# FlightControl.net
KiCad netlist of a schematic drawn in EAGLE
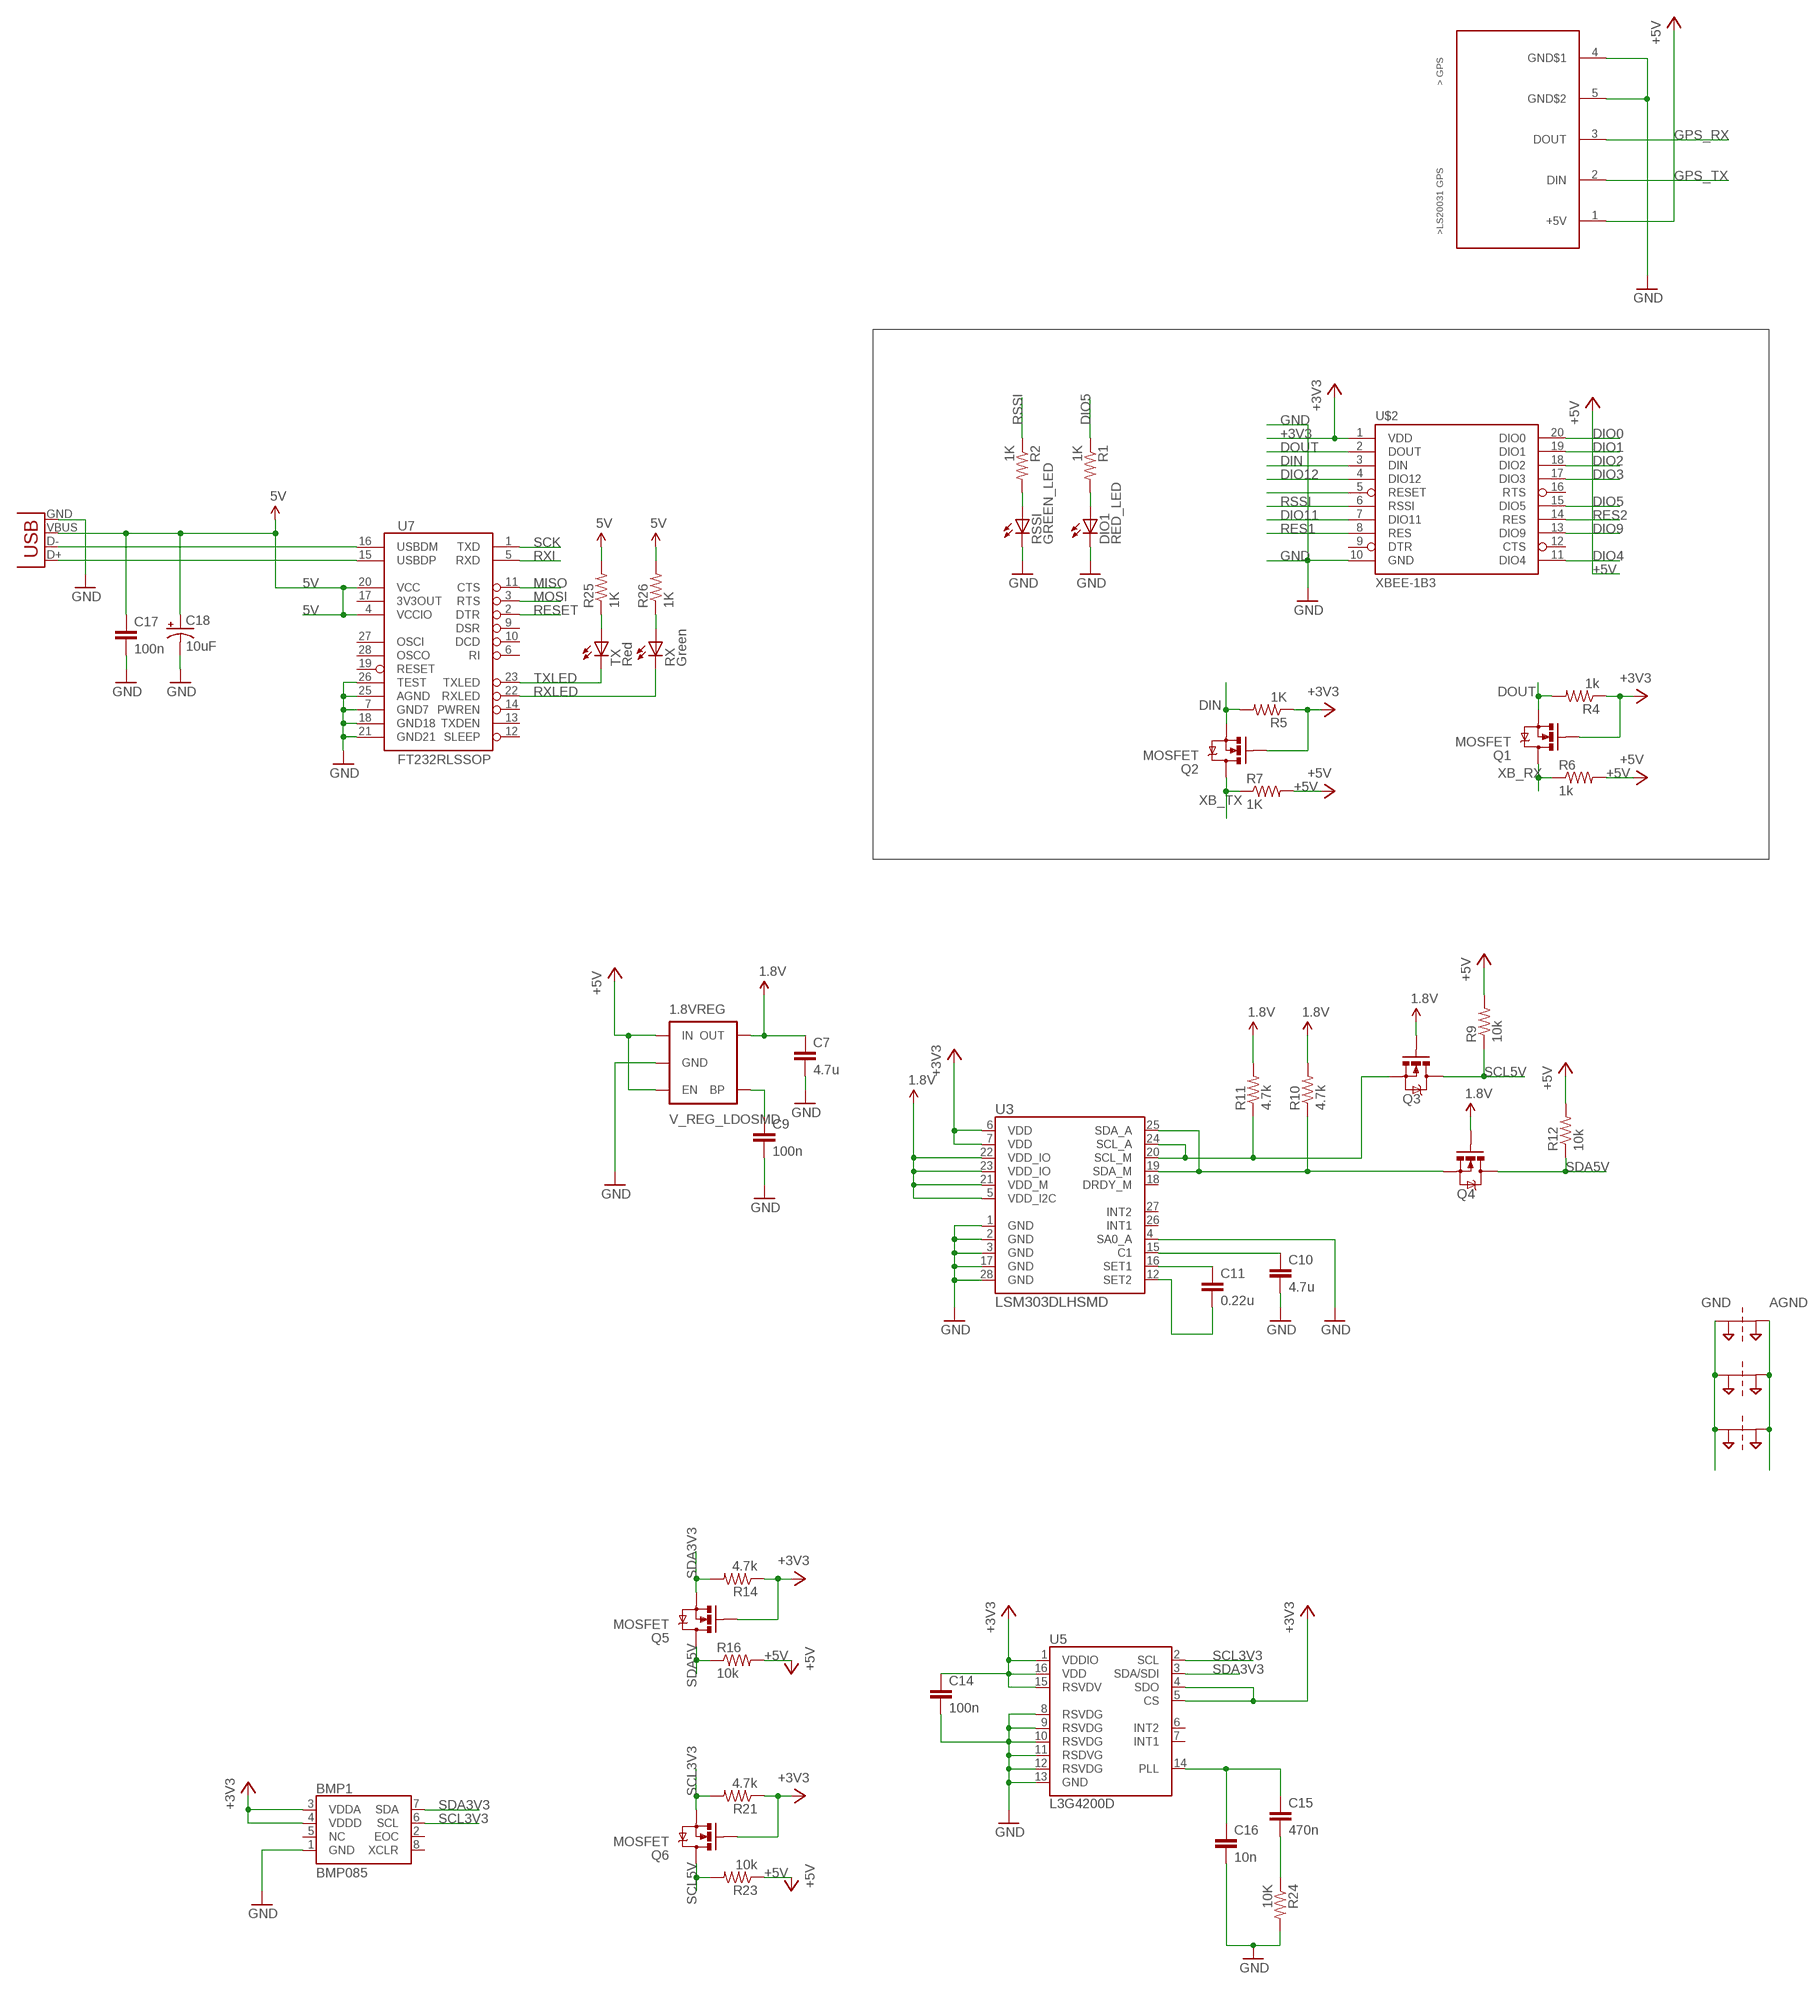
[diagram p0: schematic, sheet 1, part 1 of 2]
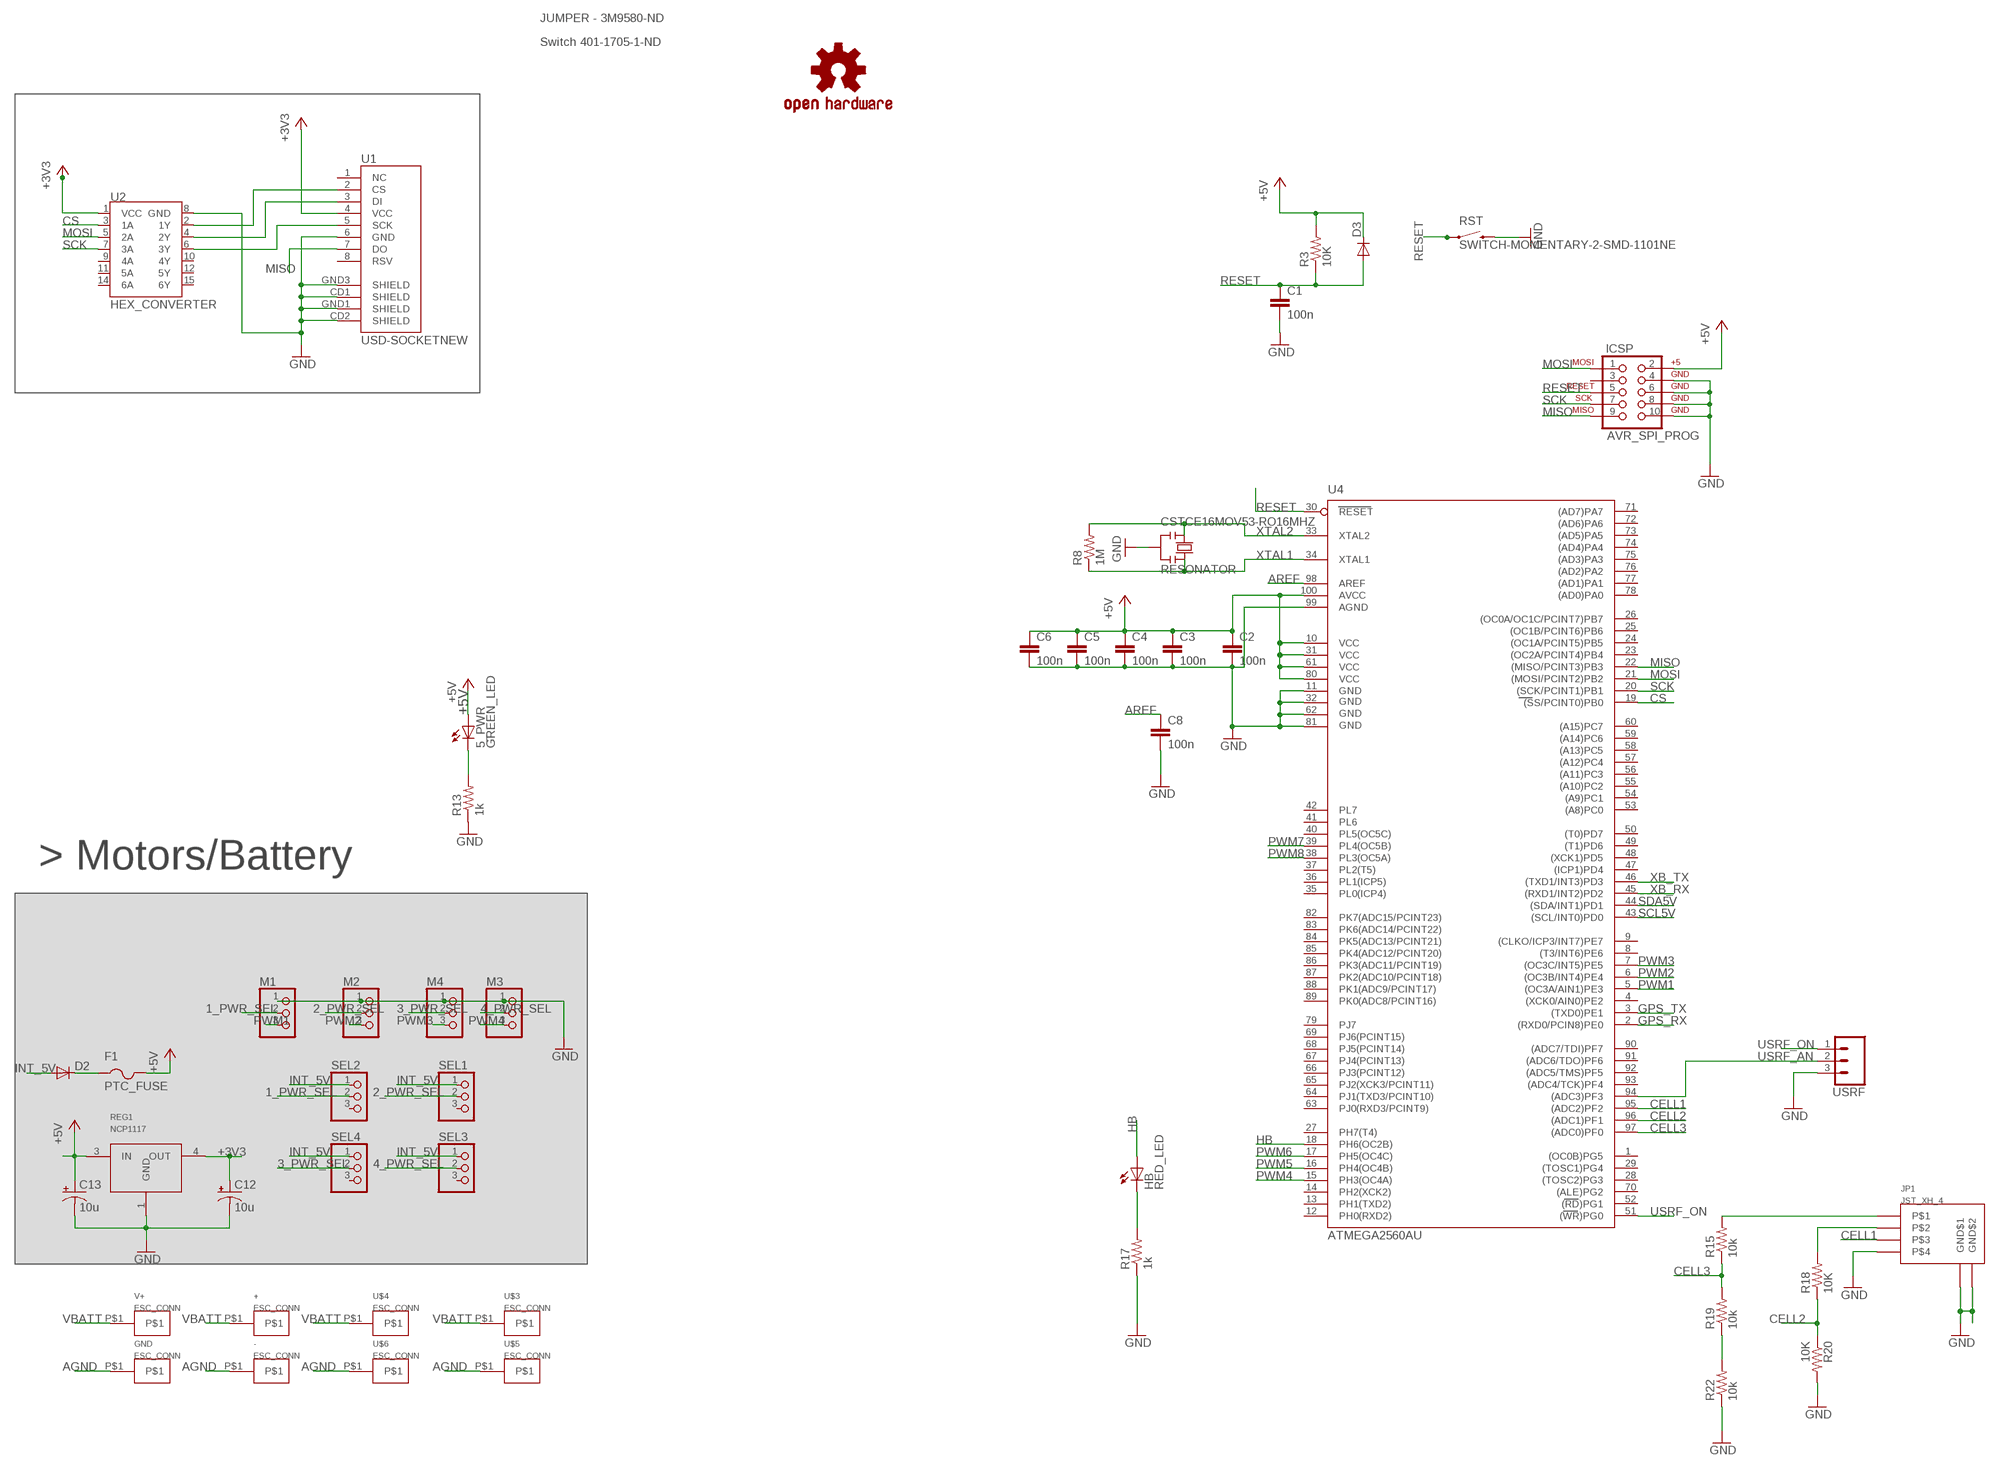
[diagram p1: schematic, sheet 1, part 2 of 2]

(export (version "E")
  (design (tool "Eeschema 10.0.6"))
  (components
    (comp (ref "+")
      (value "ESC_CONN")
      (footprint "eagle-import:ESC_CONN")
      (libsource (lib "eagle-import") (part "ESC_CONN"))
    )
    (comp (ref "-")
      (value "ESC_CONN")
      (footprint "eagle-import:ESC_CONN")
      (libsource (lib "eagle-import") (part "ESC_CONN"))
    )
    (comp (ref "1.8VREG")
      (value "V_REG_LDOSMD")
      (footprint "eagle-import:SOT23-5")
      (libsource (lib "eagle-import") (part "V_REG_LDOSMD"))
    )
    (comp (ref "5_PWR")
      (value "GREEN_LED")
      (footprint "eagle-import:LED-0603")
      (libsource (lib "eagle-import") (part "SparkFun-LED_LED0603"))
    )
    (comp (ref "BMP1")
      (value "BMP085")
      (footprint "eagle-import:BMP085")
      (libsource (lib "eagle-import") (part "BMP085"))
    )
    (comp (ref "C1")
      (value "100n")
      (footprint "eagle-import:0402-CAP")
      (libsource (lib "eagle-import") (part "SparkFun-Passives_CAP0402-CAP"))
    )
    (comp (ref "C2")
      (value "100n")
      (footprint "eagle-import:0402-CAP")
      (libsource (lib "eagle-import") (part "SparkFun-Passives_CAP0402-CAP"))
    )
    (comp (ref "C3")
      (value "100n")
      (footprint "eagle-import:0402-CAP")
      (libsource (lib "eagle-import") (part "SparkFun-Passives_CAP0402-CAP"))
    )
    (comp (ref "C4")
      (value "100n")
      (footprint "eagle-import:0402-CAP")
      (libsource (lib "eagle-import") (part "SparkFun-Passives_CAP0402-CAP"))
    )
    (comp (ref "C5")
      (value "100n")
      (footprint "eagle-import:0402-CAP")
      (libsource (lib "eagle-import") (part "SparkFun-Passives_CAP0402-CAP"))
    )
    (comp (ref "C6")
      (value "100n")
      (footprint "eagle-import:0402-CAP")
      (libsource (lib "eagle-import") (part "SparkFun-Passives_CAP0402-CAP"))
    )
    (comp (ref "C7")
      (value "4.7u")
      (footprint "eagle-import:0402-CAP")
      (libsource (lib "eagle-import") (part "SparkFun-Passives_CAP0402-CAP"))
    )
    (comp (ref "C8")
      (value "100n")
      (footprint "eagle-import:0402-CAP")
      (libsource (lib "eagle-import") (part "SparkFun-Passives_CAP0402-CAP"))
    )
    (comp (ref "C9")
      (value "100n")
      (footprint "eagle-import:0402-CAP")
      (libsource (lib "eagle-import") (part "SparkFun-Passives_CAP0402-CAP"))
    )
    (comp (ref "C10")
      (value "4.7u")
      (footprint "eagle-import:0402-CAP")
      (libsource (lib "eagle-import") (part "SparkFun-Passives_CAP0402-CAP"))
    )
    (comp (ref "C11")
      (value "0.22u")
      (footprint "eagle-import:0402-CAP")
      (libsource (lib "eagle-import") (part "SparkFun-Passives_CAP0402-CAP"))
    )
    (comp (ref "C12")
      (value "10u")
      (footprint "eagle-import:EIA3216")
      (libsource (lib "eagle-import") (part "SparkFun-Capacitors_CAP_POL1206"))
    )
    (comp (ref "C13")
      (value "10u")
      (footprint "eagle-import:EIA3216")
      (libsource (lib "eagle-import") (part "SparkFun-Capacitors_CAP_POL1206"))
    )
    (comp (ref "C14")
      (value "100n")
      (footprint "eagle-import:0402-CAP")
      (libsource (lib "eagle-import") (part "SparkFun-Capacitors_CAP0402-CAP"))
    )
    (comp (ref "C15")
      (value "470n")
      (footprint "eagle-import:0402-CAP")
      (libsource (lib "eagle-import") (part "SparkFun-Passives_CAP0402-CAP"))
    )
    (comp (ref "C16")
      (value "10n")
      (footprint "eagle-import:0402-CAP")
      (libsource (lib "eagle-import") (part "SparkFun-Passives_CAP0402-CAP"))
    )
    (comp (ref "C17")
      (value "100n")
      (footprint "eagle-import:0402-CAP")
      (libsource (lib "eagle-import") (part "CAP0402-CAP"))
    )
    (comp (ref "C18")
      (value "10uF")
      (footprint "eagle-import:EIA3216")
      (libsource (lib "eagle-import") (part "CAP_POL1206"))
    )
    (comp (ref "CSTCE16MOV53-RO16MHZ")
      (value "RESONATOR")
      (footprint "eagle-import:RESONATOR")
      (libsource (lib "eagle-import") (part "RESONATORMU"))
    )
    (comp (ref "D2")
      (value "SCHOTTKY-1206D1206")
      (footprint "eagle-import:C1206")
      (libsource (lib "eagle-import") (part "SCHOTTKY-1206D1206"))
    )
    (comp (ref "D3")
      (value "SCHOTTKY-1206D1206")
      (footprint "eagle-import:C1206")
      (libsource (lib "eagle-import") (part "SCHOTTKY-1206D1206"))
    )
    (comp (ref "DIO1")
      (value "RED_LED")
      (footprint "eagle-import:LED-0603")
      (libsource (lib "eagle-import") (part "SparkFun-LED_LED0603"))
    )
    (comp (ref "F1")
      (value "PTC_FUSE")
      (footprint "eagle-import:1812")
      (libsource (lib "eagle-import") (part "PTCFUSE-1812"))
    )
    (comp (ref "GND")
      (value "ESC_CONN")
      (footprint "eagle-import:ESC_CONN")
      (libsource (lib "eagle-import") (part "ESC_CONN"))
    )
    (comp (ref "HB")
      (value "RED_LED")
      (footprint "eagle-import:LED-0603")
      (libsource (lib "eagle-import") (part "SparkFun-LED_LED0603"))
    )
    (comp (ref "ICSP")
      (value "AVR_SPI_PROG")
      (footprint "eagle-import:AVR_ICSP")
      (libsource (lib "eagle-import") (part "AVR_SPI_PROG"))
    )
    (comp (ref "JP1")
      (value "JST_XH_4")
      (footprint "eagle-import:JST-XH4")
      (libsource (lib "eagle-import") (part "JST_XH_4"))
    )
    (comp (ref "LOGO1")
      (value "OSHW-LOGOL")
      (footprint "eagle-import:OSHW-LOGO-L")
      (libsource (lib "eagle-import") (part "OSHW-LOGOL"))
    )
    (comp (ref "M1")
      (value "PINHD-1X3")
      (footprint "eagle-import:1X03")
      (libsource (lib "eagle-import") (part "PINHD-1X3"))
    )
    (comp (ref "M2")
      (value "PINHD-1X3")
      (footprint "eagle-import:1X03")
      (libsource (lib "eagle-import") (part "PINHD-1X3"))
    )
    (comp (ref "M3")
      (value "PINHD-1X3")
      (footprint "eagle-import:1X03")
      (libsource (lib "eagle-import") (part "PINHD-1X3"))
    )
    (comp (ref "M4")
      (value "PINHD-1X3")
      (footprint "eagle-import:1X03")
      (libsource (lib "eagle-import") (part "PINHD-1X3"))
    )
    (comp (ref "PT1")
      (value "2PT_GND_TIE")
      (footprint "eagle-import:2PT_GND_TIE")
      (libsource (lib "eagle-import") (part "2PT_GND_TIE"))
    )
    (comp (ref "PT2")
      (value "2PT_GND_TIE")
      (footprint "eagle-import:2PT_GND_TIE")
      (libsource (lib "eagle-import") (part "2PT_GND_TIE"))
    )
    (comp (ref "PT3")
      (value "2PT_GND_TIE")
      (footprint "eagle-import:2PT_GND_TIE")
      (libsource (lib "eagle-import") (part "2PT_GND_TIE"))
    )
    (comp (ref "Q1")
      (value "MOSFET")
      (footprint "eagle-import:SOT23")
      (libsource (lib "eagle-import") (part "MOSFET-NCHANNELBSS138"))
    )
    (comp (ref "Q2")
      (value "MOSFET")
      (footprint "eagle-import:SOT23")
      (libsource (lib "eagle-import") (part "MOSFET-NCHANNELBSS138"))
    )
    (comp (ref "Q3")
      (value "MOSFET")
      (footprint "eagle-import:SOT23")
      (libsource (lib "eagle-import") (part "MOSFET-NCHANNELBSS138"))
    )
    (comp (ref "Q4")
      (value "MOSFET")
      (footprint "eagle-import:SOT23")
      (libsource (lib "eagle-import") (part "MOSFET-NCHANNELBSS138"))
    )
    (comp (ref "Q5")
      (value "MOSFET")
      (footprint "eagle-import:SOT23")
      (libsource (lib "eagle-import") (part "MOSFET-NCHANNELBSS138"))
    )
    (comp (ref "Q6")
      (value "MOSFET")
      (footprint "eagle-import:SOT23")
      (libsource (lib "eagle-import") (part "MOSFET-NCHANNELBSS138"))
    )
    (comp (ref "R1")
      (value "1K")
      (footprint "eagle-import:0603-RES")
      (libsource (lib "eagle-import") (part "RESISTOR0603-RES"))
    )
    (comp (ref "R2")
      (value "1K")
      (footprint "eagle-import:0603-RES")
      (libsource (lib "eagle-import") (part "RESISTOR0603-RES"))
    )
    (comp (ref "R3")
      (value "10K")
      (footprint "eagle-import:0603-RES")
      (libsource (lib "eagle-import") (part "RESISTOR0603-RES"))
    )
    (comp (ref "R4")
      (value "1k")
      (footprint "eagle-import:0603-RES")
      (libsource (lib "eagle-import") (part "RESISTOR0603-RES"))
    )
    (comp (ref "R5")
      (value "1K")
      (footprint "eagle-import:0603-RES")
      (libsource (lib "eagle-import") (part "RESISTOR0603-RES"))
    )
    (comp (ref "R6")
      (value "1k")
      (footprint "eagle-import:0603-RES")
      (libsource (lib "eagle-import") (part "RESISTOR0603-RES"))
    )
    (comp (ref "R7")
      (value "1K")
      (footprint "eagle-import:0603-RES")
      (libsource (lib "eagle-import") (part "RESISTOR0603-RES"))
    )
    (comp (ref "R8")
      (value "1M")
      (footprint "eagle-import:0603-RES")
      (libsource (lib "eagle-import") (part "RESISTOR0603-RES"))
    )
    (comp (ref "R9")
      (value "10k")
      (footprint "eagle-import:0603-RES")
      (libsource (lib "eagle-import") (part "RESISTOR0603-RES"))
    )
    (comp (ref "R10")
      (value "4.7k")
      (footprint "eagle-import:0402-RES")
      (libsource (lib "eagle-import") (part "RESISTOR0402-RES"))
    )
    (comp (ref "R11")
      (value "4.7k")
      (footprint "eagle-import:0603-RES")
      (libsource (lib "eagle-import") (part "RESISTOR0603-RES"))
    )
    (comp (ref "R12")
      (value "10k")
      (footprint "eagle-import:0603-RES")
      (libsource (lib "eagle-import") (part "RESISTOR0603-RES"))
    )
    (comp (ref "R13")
      (value "1k")
      (footprint "eagle-import:0603-RES")
      (libsource (lib "eagle-import") (part "RESISTOR0603-RES"))
    )
    (comp (ref "R14")
      (value "4.7k")
      (footprint "eagle-import:0603-RES")
      (libsource (lib "eagle-import") (part "RESISTOR0603-RES"))
    )
    (comp (ref "R15")
      (value "10k")
      (footprint "eagle-import:0603-RES")
      (libsource (lib "eagle-import") (part "RESISTOR0603-RES"))
    )
    (comp (ref "R16")
      (value "10k")
      (footprint "eagle-import:0603-RES")
      (libsource (lib "eagle-import") (part "RESISTOR0603-RES"))
    )
    (comp (ref "R17")
      (value "1k")
      (footprint "eagle-import:0603-RES")
      (libsource (lib "eagle-import") (part "RESISTOR0603-RES"))
    )
    (comp (ref "R18")
      (value "10K")
      (footprint "eagle-import:0603-RES")
      (libsource (lib "eagle-import") (part "RESISTOR0603-RES"))
    )
    (comp (ref "R19")
      (value "10k")
      (footprint "eagle-import:0603-RES")
      (libsource (lib "eagle-import") (part "RESISTOR0603-RES"))
    )
    (comp (ref "R20")
      (value "10K")
      (footprint "eagle-import:0603-RES")
      (libsource (lib "eagle-import") (part "RESISTOR0603-RES"))
    )
    (comp (ref "R21")
      (value "4.7k")
      (footprint "eagle-import:0603-RES")
      (libsource (lib "eagle-import") (part "RESISTOR0603-RES"))
    )
    (comp (ref "R22")
      (value "10k")
      (footprint "eagle-import:0603-RES")
      (libsource (lib "eagle-import") (part "RESISTOR0603-RES"))
    )
    (comp (ref "R23")
      (value "10k")
      (footprint "eagle-import:0603-RES")
      (libsource (lib "eagle-import") (part "RESISTOR0603-RES"))
    )
    (comp (ref "R24")
      (value "10K")
      (footprint "eagle-import:0603-RES")
      (libsource (lib "eagle-import") (part "RESISTOR0603-RES"))
    )
    (comp (ref "R25")
      (value "1K")
      (footprint "eagle-import:0603-RES")
      (libsource (lib "eagle-import") (part "RESISTOR0603-RES"))
    )
    (comp (ref "R26")
      (value "1K")
      (footprint "eagle-import:0603-RES")
      (libsource (lib "eagle-import") (part "RESISTOR0603-RES"))
    )
    (comp (ref "REG1")
      (value "NCP1117")
      (footprint "eagle-import:DPAK")
      (libsource (lib "eagle-import") (part "NCP1117"))
    )
    (comp (ref "RSSI")
      (value "GREEN_LED")
      (footprint "eagle-import:LED-0603")
      (libsource (lib "eagle-import") (part "SparkFun-LED_LED0603"))
    )
    (comp (ref "RST")
      (value "SWITCH-MOMENTARY-2-SMD-1101NE")
      (footprint "eagle-import:TACTILE-SWITCH-1101NE")
      (libsource (lib "eagle-import") (part "SWITCH-MOMENTARY-2-SMD-1101NE"))
    )
    (comp (ref "RX")
      (value "Green")
      (footprint "eagle-import:LED-0603")
      (libsource (lib "eagle-import") (part "LED0603"))
    )
    (comp (ref "SEL1")
      (value "PINHD-1X3")
      (footprint "eagle-import:1X03")
      (libsource (lib "eagle-import") (part "PINHD-1X3"))
    )
    (comp (ref "SEL2")
      (value "PINHD-1X3")
      (footprint "eagle-import:1X03")
      (libsource (lib "eagle-import") (part "PINHD-1X3"))
    )
    (comp (ref "SEL3")
      (value "PINHD-1X3")
      (footprint "eagle-import:1X03")
      (libsource (lib "eagle-import") (part "PINHD-1X3"))
    )
    (comp (ref "SEL4")
      (value "PINHD-1X3")
      (footprint "eagle-import:1X03")
      (libsource (lib "eagle-import") (part "PINHD-1X3"))
    )
    (comp (ref "TX")
      (value "Red")
      (footprint "eagle-import:LED-0603")
      (libsource (lib "eagle-import") (part "LED0603"))
    )
    (comp (ref "U$1")
      (value "LS20031")
      (footprint "eagle-import:LS20031")
      (libsource (lib "eagle-import") (part "LS20031"))
    )
    (comp (ref "U$2")
      (value "XBEE-1B3")
      (footprint "eagle-import:XBEE-SMD")
      (libsource (lib "eagle-import") (part "XBEE-1B3"))
    )
    (comp (ref "U$3")
      (value "ESC_CONN")
      (footprint "eagle-import:ESC_CONN")
      (libsource (lib "eagle-import") (part "ESC_CONN"))
    )
    (comp (ref "U$4")
      (value "ESC_CONN")
      (footprint "eagle-import:ESC_CONN")
      (libsource (lib "eagle-import") (part "ESC_CONN"))
    )
    (comp (ref "U$5")
      (value "ESC_CONN")
      (footprint "eagle-import:ESC_CONN")
      (libsource (lib "eagle-import") (part "ESC_CONN"))
    )
    (comp (ref "U$6")
      (value "ESC_CONN")
      (footprint "eagle-import:ESC_CONN")
      (libsource (lib "eagle-import") (part "ESC_CONN"))
    )
    (comp (ref "U1")
      (value "USD-SOCKETNEW")
      (footprint "eagle-import:MICRO-SD-SOCKET-PP")
      (libsource (lib "eagle-import") (part "USD-SOCKETNEW"))
    )
    (comp (ref "U2")
      (value "HEX_CONVERTER")
      (footprint "eagle-import:SO016")
      (libsource (lib "eagle-import") (part "HEX_CONVERTER"))
    )
    (comp (ref "U3")
      (value "LSM303DLHSMD")
      (footprint "eagle-import:LGA28-5X5")
      (libsource (lib "eagle-import") (part "LSM303DLHSMD"))
    )
    (comp (ref "U4")
      (value "ATMEGA2560AU")
      (footprint "eagle-import:TQFP100")
      (libsource (lib "eagle-import") (part "ATMEGA2560AU"))
    )
    (comp (ref "U5")
      (value "L3G4200D")
      (footprint "eagle-import:LGA16-4X4")
      (libsource (lib "eagle-import") (part "L3G4200D"))
    )
    (comp (ref "U7")
      (value "FT232RLSSOP")
      (footprint "eagle-import:SSOP28DB")
      (libsource (lib "eagle-import") (part "FT232RLSSOP"))
    )
    (comp (ref "USRF")
      (value "M03LOCK")
      (footprint "eagle-import:1X03_LOCK")
      (libsource (lib "eagle-import") (part "M03LOCK"))
    )
    (comp (ref "V+")
      (value "ESC_CONN")
      (footprint "eagle-import:ESC_CONN")
      (libsource (lib "eagle-import") (part "ESC_CONN"))
    )
    (comp (ref "X2")
      (value "USB-SMD-NS")
      (footprint "eagle-import:USB-MINIB-NOSTOP")
      (libsource (lib "eagle-import") (part "USB-SMD-NS"))
    )
  )
  (nets
    (net (code "1") (name "+3V3") (class "Default")
      (node (ref "BMP1") (pin "3") (pinfunction "VDDA_3") (pintype "power_in"))
      (node (ref "BMP1") (pin "4") (pinfunction "VDDD_4") (pintype "power_in"))
      (node (ref "C12") (pin "A") (pinfunction "+_A") (pintype "passive"))
      (node (ref "C14") (pin "1") (pinfunction "1_1") (pintype "passive"))
      (node (ref "Q1") (pin "1") (pinfunction "G_1") (pintype "passive"))
      (node (ref "Q2") (pin "1") (pinfunction "G_1") (pintype "passive"))
      (node (ref "Q5") (pin "1") (pinfunction "G_1") (pintype "passive"))
      (node (ref "Q6") (pin "1") (pinfunction "G_1") (pintype "passive"))
      (node (ref "R14") (pin "1") (pinfunction "1_1") (pintype "passive"))
      (node (ref "R21") (pin "1") (pinfunction "1_1") (pintype "passive"))
      (node (ref "R4") (pin "1") (pinfunction "1_1") (pintype "passive"))
      (node (ref "R5") (pin "1") (pinfunction "1_1") (pintype "passive"))
      (node (ref "REG1") (pin "4") (pinfunction "OUT_4") (pintype "bidirectional"))
      (node (ref "U$2") (pin "1") (pinfunction "VDD_1") (pintype "power_in"))
      (node (ref "U1") (pin "4") (pinfunction "VCC_4") (pintype "bidirectional"))
      (node (ref "U2") (pin "1") (pinfunction "VCC_1") (pintype "bidirectional"))
      (node (ref "U3") (pin "6") (pinfunction "VDD_6") (pintype "bidirectional"))
      (node (ref "U3") (pin "7") (pinfunction "VDD_7") (pintype "bidirectional"))
      (node (ref "U5") (pin "1") (pinfunction "VDDIO_1") (pintype "bidirectional"))
      (node (ref "U5") (pin "15") (pinfunction "RSVDV_15") (pintype "bidirectional"))
      (node (ref "U5") (pin "16") (pinfunction "VDD_16") (pintype "bidirectional"))
      (node (ref "U5") (pin "4") (pinfunction "SDO_4") (pintype "bidirectional"))
      (node (ref "U5") (pin "5") (pinfunction "CS_5") (pintype "bidirectional"))
    )
    (net (code "2") (name "+5V") (class "Default")
      (node (ref "1.8VREG") (pin "1") (pinfunction "IN_1") (pintype "input"))
      (node (ref "1.8VREG") (pin "3") (pinfunction "EN_3") (pintype "input"))
      (node (ref "5_PWR") (pin "A") (pinfunction "A_A") (pintype "passive"))
      (node (ref "C13") (pin "A") (pinfunction "+_A") (pintype "passive"))
      (node (ref "C2") (pin "1") (pinfunction "1_1") (pintype "passive"))
      (node (ref "C3") (pin "1") (pinfunction "1_1") (pintype "passive"))
      (node (ref "C4") (pin "1") (pinfunction "1_1") (pintype "passive"))
      (node (ref "C5") (pin "1") (pinfunction "1_1") (pintype "passive"))
      (node (ref "C6") (pin "1") (pinfunction "1_1") (pintype "passive"))
      (node (ref "D3") (pin "2") (pinfunction "C_2") (pintype "passive"))
      (node (ref "F1") (pin "2") (pinfunction "2_2") (pintype "passive"))
      (node (ref "ICSP") (pin "2") (pinfunction "2_2") (pintype "passive"))
      (node (ref "R12") (pin "2") (pinfunction "2_2") (pintype "passive"))
      (node (ref "R16") (pin "2") (pinfunction "2_2") (pintype "passive"))
      (node (ref "R23") (pin "1") (pinfunction "1_1") (pintype "passive"))
      (node (ref "R3") (pin "2") (pinfunction "2_2") (pintype "passive"))
      (node (ref "R6") (pin "2") (pinfunction "2_2") (pintype "passive"))
      (node (ref "R7") (pin "2") (pinfunction "2_2") (pintype "passive"))
      (node (ref "R9") (pin "2") (pinfunction "2_2") (pintype "passive"))
      (node (ref "REG1") (pin "3") (pinfunction "IN_3") (pintype "bidirectional"))
      (node (ref "U$1") (pin "1") (pinfunction "+5V_1") (pintype "bidirectional"))
      (node (ref "U4") (pin "10") (pinfunction "VCC_10") (pintype "power_in"))
      (node (ref "U4") (pin "100") (pinfunction "AVCC_100") (pintype "power_in"))
      (node (ref "U4") (pin "31") (pinfunction "VCC1_31") (pintype "power_in"))
      (node (ref "U4") (pin "61") (pinfunction "VCC2_61") (pintype "power_in"))
      (node (ref "U4") (pin "80") (pinfunction "VCC3_80") (pintype "power_in"))
    )
    (net (code "3") (name "/1_PWR_SEL") (class "Default")
      (node (ref "M1") (pin "2") (pinfunction "2_2") (pintype "passive"))
      (node (ref "SEL2") (pin "2") (pinfunction "2_2") (pintype "passive"))
    )
    (net (code "4") (name "/2_PWR_SEL") (class "Default")
      (node (ref "M2") (pin "2") (pinfunction "2_2") (pintype "passive"))
      (node (ref "SEL1") (pin "2") (pinfunction "2_2") (pintype "passive"))
    )
    (net (code "5") (name "/3_PWR_SEL") (class "Default")
      (node (ref "M4") (pin "2") (pinfunction "2_2") (pintype "passive"))
      (node (ref "SEL4") (pin "2") (pinfunction "2_2") (pintype "passive"))
    )
    (net (code "6") (name "/4_PWR_SEL") (class "Default")
      (node (ref "M3") (pin "2") (pinfunction "2_2") (pintype "passive"))
      (node (ref "SEL3") (pin "2") (pinfunction "2_2") (pintype "passive"))
    )
    (net (code "7") (name "/AGND") (class "Default")
      (node (ref "-") (pin "P$1") (pinfunction "P$1_P$1") (pintype "bidirectional"))
      (node (ref "GND") (pin "P$1") (pinfunction "P$1_P$1") (pintype "bidirectional"))
      (node (ref "PT1") (pin "P$2") (pinfunction "P$2_P$2") (pintype "bidirectional"))
      (node (ref "PT2") (pin "P$2") (pinfunction "P$2_P$2") (pintype "bidirectional"))
      (node (ref "PT3") (pin "P$2") (pinfunction "P$2_P$2") (pintype "bidirectional"))
      (node (ref "U$5") (pin "P$1") (pinfunction "P$1_P$1") (pintype "bidirectional"))
      (node (ref "U$6") (pin "P$1") (pinfunction "P$1_P$1") (pintype "bidirectional"))
    )
    (net (code "8") (name "/AREF") (class "Default")
      (node (ref "C8") (pin "1") (pinfunction "1_1") (pintype "passive"))
      (node (ref "U4") (pin "98") (pinfunction "AREF_98") (pintype "bidirectional"))
    )
    (net (code "9") (name "/CELL1") (class "Default")
      (node (ref "JP1") (pin "P$3") (pinfunction "P$3_P$3") (pintype "bidirectional"))
      (node (ref "U4") (pin "95") (pinfunction "(ADC2)PF2_95") (pintype "bidirectional"))
    )
    (net (code "10") (name "/CELL2") (class "Default")
      (node (ref "R18") (pin "1") (pinfunction "1_1") (pintype "passive"))
      (node (ref "R20") (pin "1") (pinfunction "1_1") (pintype "passive"))
      (node (ref "U4") (pin "96") (pinfunction "(ADC1)PF1_96") (pintype "bidirectional"))
    )
    (net (code "11") (name "/CELL3") (class "Default")
      (node (ref "R15") (pin "1") (pinfunction "1_1") (pintype "passive"))
      (node (ref "R19") (pin "2") (pinfunction "2_2") (pintype "passive"))
      (node (ref "U4") (pin "97") (pinfunction "(ADC0)PF0_97") (pintype "bidirectional"))
    )
    (net (code "12") (name "/CS") (class "Default")
      (node (ref "U2") (pin "3") (pinfunction "1A_3") (pintype "bidirectional"))
      (node (ref "U4") (pin "19") (pinfunction "(SS/PCINT0)PB0_19") (pintype "bidirectional"))
    )
    (net (code "13") (name "/DIN") (class "Default")
      (node (ref "Q2") (pin "2") (pinfunction "S_2") (pintype "passive"))
      (node (ref "R5") (pin "2") (pinfunction "2_2") (pintype "passive"))
      (node (ref "U$2") (pin "3") (pinfunction "DIN_3") (pintype "input"))
    )
    (net (code "14") (name "/DIO0") (class "Default")
      (node (ref "U$2") (pin "20") (pinfunction "DIO0_20") (pintype "bidirectional"))
    )
    (net (code "15") (name "/DIO1") (class "Default")
      (node (ref "U$2") (pin "19") (pinfunction "DIO1_19") (pintype "bidirectional"))
    )
    (net (code "16") (name "/DIO2") (class "Default")
      (node (ref "U$2") (pin "18") (pinfunction "DIO2_18") (pintype "bidirectional"))
    )
    (net (code "17") (name "/DIO3") (class "Default")
      (node (ref "U$2") (pin "17") (pinfunction "DIO3_17") (pintype "bidirectional"))
    )
    (net (code "18") (name "/DIO4") (class "Default")
      (node (ref "U$2") (pin "11") (pinfunction "DIO4_11") (pintype "bidirectional"))
    )
    (net (code "19") (name "/DIO5") (class "Default")
      (node (ref "R1") (pin "1") (pinfunction "1_1") (pintype "passive"))
      (node (ref "U$2") (pin "15") (pinfunction "DIO5_15") (pintype "bidirectional"))
    )
    (net (code "20") (name "/DIO9") (class "Default")
      (node (ref "U$2") (pin "13") (pinfunction "DIO9_13") (pintype "bidirectional"))
    )
    (net (code "21") (name "/DIO11") (class "Default")
      (node (ref "U$2") (pin "7") (pinfunction "DIO11_7") (pintype "bidirectional"))
    )
    (net (code "22") (name "/DIO12") (class "Default")
      (node (ref "U$2") (pin "4") (pinfunction "DIO12_4") (pintype "bidirectional"))
    )
    (net (code "23") (name "/DOUT") (class "Default")
      (node (ref "Q1") (pin "2") (pinfunction "S_2") (pintype "passive"))
      (node (ref "R4") (pin "2") (pinfunction "2_2") (pintype "passive"))
      (node (ref "U$2") (pin "2") (pinfunction "DOUT_2") (pintype "output"))
    )
    (net (code "24") (name "/GPS_RX") (class "Default")
      (node (ref "U$1") (pin "3") (pinfunction "DOUT_3") (pintype "output"))
      (node (ref "U4") (pin "2") (pinfunction "(RXD0/PCIN8)PE0_2") (pintype "bidirectional"))
    )
    (net (code "25") (name "/GPS_TX") (class "Default")
      (node (ref "U$1") (pin "2") (pinfunction "DIN_2") (pintype "bidirectional"))
      (node (ref "U4") (pin "3") (pinfunction "(TXD0)PE1_3") (pintype "bidirectional"))
    )
    (net (code "26") (name "/HB") (class "Default")
      (node (ref "HB") (pin "A") (pinfunction "A_A") (pintype "passive"))
      (node (ref "U4") (pin "18") (pinfunction "PH6(OC2B)_18") (pintype "bidirectional"))
    )
    (net (code "27") (name "/INT_5V") (class "Default")
      (node (ref "D2") (pin "1") (pinfunction "A_1") (pintype "passive"))
      (node (ref "SEL1") (pin "1") (pinfunction "1_1") (pintype "passive"))
      (node (ref "SEL2") (pin "1") (pinfunction "1_1") (pintype "passive"))
      (node (ref "SEL3") (pin "1") (pinfunction "1_1") (pintype "passive"))
      (node (ref "SEL4") (pin "1") (pinfunction "1_1") (pintype "passive"))
    )
    (net (code "28") (name "/MISO") (class "Default")
      (node (ref "ICSP") (pin "9") (pinfunction "9_9") (pintype "passive"))
      (node (ref "U1") (pin "7") (pinfunction "DO_7") (pintype "bidirectional"))
      (node (ref "U4") (pin "22") (pinfunction "(MISO/PCINT3)PB3_22") (pintype "bidirectional"))
      (node (ref "U7") (pin "11") (pinfunction "CTS_11") (pintype "input"))
    )
    (net (code "29") (name "/MOSI") (class "Default")
      (node (ref "ICSP") (pin "1") (pinfunction "1_1") (pintype "passive"))
      (node (ref "U2") (pin "5") (pinfunction "2A_5") (pintype "bidirectional"))
      (node (ref "U4") (pin "21") (pinfunction "(MOSI/PCINT2)PB2_21") (pintype "bidirectional"))
      (node (ref "U7") (pin "3") (pinfunction "RTS_3") (pintype "output"))
    )
    (net (code "30") (name "/PWM1") (class "Default")
      (node (ref "M1") (pin "3") (pinfunction "3_3") (pintype "passive"))
      (node (ref "U4") (pin "5") (pinfunction "(OC3A/AIN1)PE3_5") (pintype "bidirectional"))
    )
    (net (code "31") (name "/PWM2") (class "Default")
      (node (ref "M2") (pin "3") (pinfunction "3_3") (pintype "passive"))
      (node (ref "U4") (pin "6") (pinfunction "(OC3B/INT4)PE4_6") (pintype "bidirectional"))
    )
    (net (code "32") (name "/PWM3") (class "Default")
      (node (ref "M4") (pin "3") (pinfunction "3_3") (pintype "passive"))
      (node (ref "U4") (pin "7") (pinfunction "(OC3C/INT5)PE5_7") (pintype "bidirectional"))
    )
    (net (code "33") (name "/PWM4") (class "Default")
      (node (ref "M3") (pin "3") (pinfunction "3_3") (pintype "passive"))
      (node (ref "U4") (pin "15") (pinfunction "PH3(OC4A)_15") (pintype "bidirectional"))
    )
    (net (code "34") (name "/PWM5") (class "Default")
      (node (ref "U4") (pin "16") (pinfunction "PH4(OC4B)_16") (pintype "bidirectional"))
    )
    (net (code "35") (name "/PWM6") (class "Default")
      (node (ref "U4") (pin "17") (pinfunction "PH5(OC4C)_17") (pintype "bidirectional"))
    )
    (net (code "36") (name "/PWM7") (class "Default")
      (node (ref "U4") (pin "39") (pinfunction "PL4(OC5B)_39") (pintype "bidirectional"))
    )
    (net (code "37") (name "/PWM8") (class "Default")
      (node (ref "U4") (pin "38") (pinfunction "PL3(OC5A)_38") (pintype "bidirectional"))
    )
    (net (code "38") (name "/RES1") (class "Default")
      (node (ref "U$2") (pin "8") (pinfunction "RES_8") (pintype "bidirectional"))
    )
    (net (code "39") (name "/RES2") (class "Default")
      (node (ref "U$2") (pin "14") (pinfunction "RES_14") (pintype "bidirectional"))
    )
    (net (code "40") (name "/RESET") (class "Default")
      (node (ref "C1") (pin "1") (pinfunction "1_1") (pintype "passive"))
      (node (ref "D3") (pin "1") (pinfunction "A_1") (pintype "passive"))
      (node (ref "ICSP") (pin "5") (pinfunction "5_5") (pintype "passive"))
      (node (ref "R3") (pin "1") (pinfunction "1_1") (pintype "passive"))
      (node (ref "RST") (pin "P$1") (pinfunction "1_P$1") (pintype "passive"))
      (node (ref "U4") (pin "30") (pinfunction "RESET_30") (pintype "input"))
      (node (ref "U7") (pin "2") (pinfunction "DTR_2") (pintype "output"))
    )
    (net (code "41") (name "/RSSI") (class "Default")
      (node (ref "R2") (pin "1") (pinfunction "1_1") (pintype "passive"))
      (node (ref "U$2") (pin "6") (pinfunction "RSSI_6") (pintype "bidirectional"))
    )
    (net (code "42") (name "/RXI") (class "Default")
      (node (ref "U7") (pin "5") (pinfunction "RXD_5") (pintype "input"))
    )
    (net (code "43") (name "/RXLED") (class "Default")
      (node (ref "RX") (pin "C") (pinfunction "C_C") (pintype "passive"))
      (node (ref "U7") (pin "22") (pinfunction "RXLED_22") (pintype "input"))
    )
    (net (code "44") (name "/SCK") (class "Default")
      (node (ref "ICSP") (pin "7") (pinfunction "7_7") (pintype "passive"))
      (node (ref "U2") (pin "7") (pinfunction "3A_7") (pintype "bidirectional"))
      (node (ref "U4") (pin "20") (pinfunction "(SCK/PCINT1)PB1_20") (pintype "bidirectional"))
      (node (ref "U7") (pin "1") (pinfunction "TXD_1") (pintype "output"))
    )
    (net (code "45") (name "/SCL3V3") (class "Default")
      (node (ref "BMP1") (pin "6") (pinfunction "SCL_6") (pintype "input"))
      (node (ref "Q6") (pin "2") (pinfunction "S_2") (pintype "passive"))
      (node (ref "R21") (pin "2") (pinfunction "2_2") (pintype "passive"))
      (node (ref "U5") (pin "2") (pinfunction "SCL_2") (pintype "bidirectional"))
    )
    (net (code "46") (name "/SCL5V") (class "Default")
      (node (ref "Q3") (pin "3") (pinfunction "D_3") (pintype "passive"))
      (node (ref "Q6") (pin "3") (pinfunction "D_3") (pintype "passive"))
      (node (ref "R23") (pin "2") (pinfunction "2_2") (pintype "passive"))
      (node (ref "R9") (pin "1") (pinfunction "1_1") (pintype "passive"))
      (node (ref "U4") (pin "43") (pinfunction "(SCL/INT0)PD0_43") (pintype "bidirectional"))
    )
    (net (code "47") (name "/SDA3V3") (class "Default")
      (node (ref "BMP1") (pin "7") (pinfunction "SDA_7") (pintype "bidirectional"))
      (node (ref "Q5") (pin "2") (pinfunction "S_2") (pintype "passive"))
      (node (ref "R14") (pin "2") (pinfunction "2_2") (pintype "passive"))
      (node (ref "U5") (pin "3") (pinfunction "SDA/SDI_3") (pintype "bidirectional"))
    )
    (net (code "48") (name "/SDA5V") (class "Default")
      (node (ref "Q4") (pin "3") (pinfunction "D_3") (pintype "passive"))
      (node (ref "Q5") (pin "3") (pinfunction "D_3") (pintype "passive"))
      (node (ref "R12") (pin "1") (pinfunction "1_1") (pintype "passive"))
      (node (ref "R16") (pin "1") (pinfunction "1_1") (pintype "passive"))
      (node (ref "U4") (pin "44") (pinfunction "(SDA/INT1)PD1_44") (pintype "bidirectional"))
    )
    (net (code "49") (name "/TXLED") (class "Default")
      (node (ref "TX") (pin "C") (pinfunction "C_C") (pintype "passive"))
      (node (ref "U7") (pin "23") (pinfunction "TXLED_23") (pintype "input"))
    )
    (net (code "50") (name "/USRF_AN") (class "Default")
      (node (ref "U4") (pin "94") (pinfunction "(ADC3)PF3_94") (pintype "bidirectional"))
      (node (ref "USRF") (pin "2") (pinfunction "2_2") (pintype "passive"))
    )
    (net (code "51") (name "/USRF_ON") (class "Default")
      (node (ref "U4") (pin "51") (pinfunction "(WR)PG0_51") (pintype "bidirectional"))
      (node (ref "USRF") (pin "1") (pinfunction "1_1") (pintype "passive"))
    )
    (net (code "52") (name "/VBATT") (class "Default")
      (node (ref "+") (pin "P$1") (pinfunction "P$1_P$1") (pintype "bidirectional"))
      (node (ref "U$3") (pin "P$1") (pinfunction "P$1_P$1") (pintype "bidirectional"))
      (node (ref "U$4") (pin "P$1") (pinfunction "P$1_P$1") (pintype "bidirectional"))
      (node (ref "V+") (pin "P$1") (pinfunction "P$1_P$1") (pintype "bidirectional"))
    )
    (net (code "53") (name "/XB_RX") (class "Default")
      (node (ref "Q1") (pin "3") (pinfunction "D_3") (pintype "passive"))
      (node (ref "R6") (pin "1") (pinfunction "1_1") (pintype "passive"))
      (node (ref "U4") (pin "45") (pinfunction "(RXD1/INT2)PD2_45") (pintype "bidirectional"))
    )
    (net (code "54") (name "/XB_TX") (class "Default")
      (node (ref "Q2") (pin "3") (pinfunction "D_3") (pintype "passive"))
      (node (ref "R7") (pin "1") (pinfunction "1_1") (pintype "passive"))
      (node (ref "U4") (pin "46") (pinfunction "(TXD1/INT3)PD3_46") (pintype "bidirectional"))
    )
    (net (code "55") (name "/XTAL1") (class "Default")
      (node (ref "CSTCE16MOV53-RO16MHZ") (pin "3") (pinfunction "3_3") (pintype "passive"))
      (node (ref "R8") (pin "1") (pinfunction "1_1") (pintype "passive"))
      (node (ref "U4") (pin "34") (pinfunction "XTAL1_34") (pintype "input"))
    )
    (net (code "56") (name "/XTAL2") (class "Default")
      (node (ref "CSTCE16MOV53-RO16MHZ") (pin "1") (pinfunction "1_1") (pintype "passive"))
      (node (ref "R8") (pin "2") (pinfunction "2_2") (pintype "passive"))
      (node (ref "U4") (pin "33") (pinfunction "XTAL2_33") (pintype "output"))
    )
    (net (code "57") (name "1.8V") (class "Default")
      (node (ref "1.8VREG") (pin "5") (pinfunction "OUT_5") (pintype "passive"))
      (node (ref "C7") (pin "1") (pinfunction "1_1") (pintype "passive"))
      (node (ref "Q3") (pin "1") (pinfunction "G_1") (pintype "passive"))
      (node (ref "Q4") (pin "1") (pinfunction "G_1") (pintype "passive"))
      (node (ref "R10") (pin "2") (pinfunction "2_2") (pintype "passive"))
      (node (ref "R11") (pin "2") (pinfunction "2_2") (pintype "passive"))
      (node (ref "U3") (pin "21") (pinfunction "VDD_M_21") (pintype "bidirectional"))
      (node (ref "U3") (pin "22") (pinfunction "VDD_IO_22") (pintype "bidirectional"))
      (node (ref "U3") (pin "23") (pinfunction "VDD_IO_23") (pintype "bidirectional"))
      (node (ref "U3") (pin "5") (pinfunction "VDD_I2C_5") (pintype "bidirectional"))
    )
    (net (code "58") (name "5V") (class "Default")
      (node (ref "C17") (pin "1") (pinfunction "1_1") (pintype "passive"))
      (node (ref "C18") (pin "A") (pinfunction "+_A") (pintype "passive"))
      (node (ref "R25") (pin "2") (pinfunction "2_2") (pintype "passive"))
      (node (ref "R26") (pin "2") (pinfunction "2_2") (pintype "passive"))
      (node (ref "U7") (pin "20") (pinfunction "VCC_20") (pintype "power_in"))
      (node (ref "U7") (pin "4") (pinfunction "VCCIO_4") (pintype "power_in"))
      (node (ref "X2") (pin "VBUS") (pinfunction "VBUS_VBUS") (pintype "bidirectional"))
    )
    (net (code "59") (name "GND") (class "Default")
      (node (ref "1.8VREG") (pin "2") (pinfunction "GND_2") (pintype "input"))
      (node (ref "BMP1") (pin "1") (pinfunction "GND_1") (pintype "power_in"))
      (node (ref "C1") (pin "2") (pinfunction "2_2") (pintype "passive"))
      (node (ref "C10") (pin "2") (pinfunction "2_2") (pintype "passive"))
      (node (ref "C12") (pin "C") (pinfunction "-_C") (pintype "passive"))
      (node (ref "C13") (pin "C") (pinfunction "-_C") (pintype "passive"))
      (node (ref "C14") (pin "2") (pinfunction "2_2") (pintype "passive"))
      (node (ref "C16") (pin "2") (pinfunction "2_2") (pintype "passive"))
      (node (ref "C17") (pin "2") (pinfunction "2_2") (pintype "passive"))
      (node (ref "C18") (pin "C") (pinfunction "-_C") (pintype "passive"))
      (node (ref "C2") (pin "2") (pinfunction "2_2") (pintype "passive"))
      (node (ref "C3") (pin "2") (pinfunction "2_2") (pintype "passive"))
      (node (ref "C4") (pin "2") (pinfunction "2_2") (pintype "passive"))
      (node (ref "C5") (pin "2") (pinfunction "2_2") (pintype "passive"))
      (node (ref "C6") (pin "2") (pinfunction "2_2") (pintype "passive"))
      (node (ref "C7") (pin "2") (pinfunction "2_2") (pintype "passive"))
      (node (ref "C8") (pin "2") (pinfunction "2_2") (pintype "passive"))
      (node (ref "C9") (pin "2") (pinfunction "2_2") (pintype "passive"))
      (node (ref "CSTCE16MOV53-RO16MHZ") (pin "2") (pinfunction "2_2") (pintype "passive"))
      (node (ref "DIO1") (pin "C") (pinfunction "C_C") (pintype "passive"))
      (node (ref "ICSP") (pin "10") (pinfunction "10_10") (pintype "passive"))
      (node (ref "ICSP") (pin "4") (pinfunction "4_4") (pintype "passive"))
      (node (ref "ICSP") (pin "6") (pinfunction "6_6") (pintype "passive"))
      (node (ref "ICSP") (pin "8") (pinfunction "8_8") (pintype "passive"))
      (node (ref "JP1") (pin "GND$1") (pinfunction "GND$1_GND$1") (pintype "bidirectional"))
      (node (ref "JP1") (pin "GND$2") (pinfunction "GND$2_GND$2") (pintype "bidirectional"))
      (node (ref "JP1") (pin "P$4") (pinfunction "P$4_P$4") (pintype "bidirectional"))
      (node (ref "M1") (pin "1") (pinfunction "1_1") (pintype "passive"))
      (node (ref "M2") (pin "1") (pinfunction "1_1") (pintype "passive"))
      (node (ref "M3") (pin "1") (pinfunction "1_1") (pintype "passive"))
      (node (ref "M4") (pin "1") (pinfunction "1_1") (pintype "passive"))
      (node (ref "PT1") (pin "P$1") (pinfunction "P$1_P$1") (pintype "bidirectional"))
      (node (ref "PT2") (pin "P$1") (pinfunction "P$1_P$1") (pintype "bidirectional"))
      (node (ref "PT3") (pin "P$1") (pinfunction "P$1_P$1") (pintype "bidirectional"))
      (node (ref "R13") (pin "1") (pinfunction "1_1") (pintype "passive"))
      (node (ref "R17") (pin "1") (pinfunction "1_1") (pintype "passive"))
      (node (ref "R20") (pin "2") (pinfunction "2_2") (pintype "passive"))
      (node (ref "R22") (pin "1") (pinfunction "1_1") (pintype "passive"))
      (node (ref "R24") (pin "2") (pinfunction "2_2") (pintype "passive"))
      (node (ref "REG1") (pin "1") (pinfunction "GND_1") (pintype "bidirectional"))
      (node (ref "RSSI") (pin "C") (pinfunction "C_C") (pintype "passive"))
      (node (ref "RST") (pin "P$2") (pinfunction "2_P$2") (pintype "passive"))
      (node (ref "U$1") (pin "4") (pinfunction "GND$1_4") (pintype "bidirectional"))
      (node (ref "U$1") (pin "5") (pinfunction "GND$2_5") (pintype "bidirectional"))
      (node (ref "U$2") (pin "10") (pinfunction "GND_10") (pintype "power_in"))
      (node (ref "U1") (pin "6") (pinfunction "GND_6") (pintype "bidirectional"))
      (node (ref "U1") (pin "CD1") (pinfunction "SHIELD_CD1") (pintype "bidirectional"))
      (node (ref "U1") (pin "CD2") (pinfunction "SHIELD_CD2") (pintype "bidirectional"))
      (node (ref "U1") (pin "GND1") (pinfunction "SHIELD_GND1") (pintype "bidirectional"))
      (node (ref "U1") (pin "GND3") (pinfunction "SHIELD_GND3") (pintype "bidirectional"))
      (node (ref "U2") (pin "8") (pinfunction "GND_8") (pintype "bidirectional"))
      (node (ref "U3") (pin "1") (pinfunction "GND_1") (pintype "bidirectional"))
      (node (ref "U3") (pin "17") (pinfunction "GND_17") (pintype "bidirectional"))
      (node (ref "U3") (pin "2") (pinfunction "GND_2") (pintype "bidirectional"))
      (node (ref "U3") (pin "28") (pinfunction "GND_28") (pintype "bidirectional"))
      (node (ref "U3") (pin "3") (pinfunction "GND_3") (pintype "bidirectional"))
      (node (ref "U3") (pin "4") (pinfunction "SA0_A_4") (pintype "bidirectional"))
      (node (ref "U4") (pin "11") (pinfunction "GND_11") (pintype "power_in"))
      (node (ref "U4") (pin "32") (pinfunction "GND1_32") (pintype "power_in"))
      (node (ref "U4") (pin "62") (pinfunction "GND2_62") (pintype "power_in"))
      (node (ref "U4") (pin "81") (pinfunction "GND3_81") (pintype "power_in"))
      (node (ref "U4") (pin "99") (pinfunction "AGND_99") (pintype "power_in"))
      (node (ref "U5") (pin "10") (pinfunction "RSVDG_10") (pintype "bidirectional"))
      (node (ref "U5") (pin "11") (pinfunction "RSDVG_11") (pintype "bidirectional"))
      (node (ref "U5") (pin "12") (pinfunction "RSVDG_12") (pintype "bidirectional"))
      (node (ref "U5") (pin "13") (pinfunction "GND_13") (pintype "bidirectional"))
      (node (ref "U5") (pin "8") (pinfunction "RSVDG_8") (pintype "bidirectional"))
      (node (ref "U5") (pin "9") (pinfunction "RSVDG_9") (pintype "bidirectional"))
      (node (ref "U7") (pin "18") (pinfunction "GND18_18") (pintype "power_in"))
      (node (ref "U7") (pin "21") (pinfunction "GND21_21") (pintype "power_in"))
      (node (ref "U7") (pin "25") (pinfunction "AGND_25") (pintype "power_in"))
      (node (ref "U7") (pin "26") (pinfunction "TEST_26") (pintype "input"))
      (node (ref "U7") (pin "7") (pinfunction "GND7_7") (pintype "power_in"))
      (node (ref "USRF") (pin "3") (pinfunction "3_3") (pintype "passive"))
      (node (ref "X2") (pin "GND") (pinfunction "GND_GND") (pintype "bidirectional"))
    )
    (net (code "60") (name "Net-(1.8VREG-BP)") (class "Default")
      (node (ref "1.8VREG") (pin "4") (pinfunction "BP_4") (pintype "input"))
      (node (ref "C9") (pin "1") (pinfunction "1_1") (pintype "passive"))
    )
    (net (code "61") (name "Net-(5_PWR-PadC)") (class "Default")
      (node (ref "5_PWR") (pin "C") (pinfunction "C_C") (pintype "passive"))
      (node (ref "R13") (pin "2") (pinfunction "2_2") (pintype "passive"))
    )
    (net (code "62") (name "Net-(C15-Pad2)") (class "Default")
      (node (ref "C15") (pin "2") (pinfunction "2_2") (pintype "passive"))
      (node (ref "R24") (pin "1") (pinfunction "1_1") (pintype "passive"))
    )
    (net (code "63") (name "Net-(D2-C)") (class "Default")
      (node (ref "D2") (pin "2") (pinfunction "C_2") (pintype "passive"))
      (node (ref "F1") (pin "1") (pinfunction "1_1") (pintype "passive"))
    )
    (net (code "64") (name "Net-(DIO1-PadA)") (class "Default")
      (node (ref "DIO1") (pin "A") (pinfunction "A_A") (pintype "passive"))
      (node (ref "R1") (pin "2") (pinfunction "2_2") (pintype "passive"))
    )
    (net (code "65") (name "Net-(HB-PadC)") (class "Default")
      (node (ref "HB") (pin "C") (pinfunction "C_C") (pintype "passive"))
      (node (ref "R17") (pin "2") (pinfunction "2_2") (pintype "passive"))
    )
    (net (code "66") (name "Net-(JP1-PadP$1)") (class "Default")
      (node (ref "JP1") (pin "P$1") (pinfunction "P$1_P$1") (pintype "bidirectional"))
      (node (ref "R15") (pin "2") (pinfunction "2_2") (pintype "passive"))
    )
    (net (code "67") (name "Net-(JP1-PadP$2)") (class "Default")
      (node (ref "JP1") (pin "P$2") (pinfunction "P$2_P$2") (pintype "bidirectional"))
      (node (ref "R18") (pin "2") (pinfunction "2_2") (pintype "passive"))
    )
    (net (code "68") (name "Net-(Q3-S)") (class "Default")
      (node (ref "Q3") (pin "2") (pinfunction "S_2") (pintype "passive"))
      (node (ref "R11") (pin "1") (pinfunction "1_1") (pintype "passive"))
      (node (ref "U3") (pin "20") (pinfunction "SCL_M_20") (pintype "bidirectional"))
      (node (ref "U3") (pin "24") (pinfunction "SCL_A_24") (pintype "bidirectional"))
    )
    (net (code "69") (name "Net-(Q4-S)") (class "Default")
      (node (ref "Q4") (pin "2") (pinfunction "S_2") (pintype "passive"))
      (node (ref "R10") (pin "1") (pinfunction "1_1") (pintype "passive"))
      (node (ref "U3") (pin "19") (pinfunction "SDA_M_19") (pintype "bidirectional"))
      (node (ref "U3") (pin "25") (pinfunction "SDA_A_25") (pintype "bidirectional"))
    )
    (net (code "70") (name "Net-(R2-Pad2)") (class "Default")
      (node (ref "R2") (pin "2") (pinfunction "2_2") (pintype "passive"))
      (node (ref "RSSI") (pin "A") (pinfunction "A_A") (pintype "passive"))
    )
    (net (code "71") (name "Net-(R19-Pad1)") (class "Default")
      (node (ref "R19") (pin "1") (pinfunction "1_1") (pintype "passive"))
      (node (ref "R22") (pin "2") (pinfunction "2_2") (pintype "passive"))
    )
    (net (code "72") (name "Net-(R25-Pad1)") (class "Default")
      (node (ref "R25") (pin "1") (pinfunction "1_1") (pintype "passive"))
      (node (ref "TX") (pin "A") (pinfunction "A_A") (pintype "passive"))
    )
    (net (code "73") (name "Net-(R26-Pad1)") (class "Default")
      (node (ref "R26") (pin "1") (pinfunction "1_1") (pintype "passive"))
      (node (ref "RX") (pin "A") (pinfunction "A_A") (pintype "passive"))
    )
    (net (code "74") (name "Net-(U1-CS)") (class "Default")
      (node (ref "U1") (pin "2") (pinfunction "CS_2") (pintype "bidirectional"))
      (node (ref "U2") (pin "2") (pinfunction "1Y_2") (pintype "bidirectional"))
    )
    (net (code "75") (name "Net-(U1-DI)") (class "Default")
      (node (ref "U1") (pin "3") (pinfunction "DI_3") (pintype "bidirectional"))
      (node (ref "U2") (pin "4") (pinfunction "2Y_4") (pintype "bidirectional"))
    )
    (net (code "76") (name "Net-(U1-SCK)") (class "Default")
      (node (ref "U1") (pin "5") (pinfunction "SCK_5") (pintype "bidirectional"))
      (node (ref "U2") (pin "6") (pinfunction "3Y_6") (pintype "bidirectional"))
    )
    (net (code "77") (name "Net-(U3-C1)") (class "Default")
      (node (ref "C10") (pin "1") (pinfunction "1_1") (pintype "passive"))
      (node (ref "U3") (pin "15") (pinfunction "C1_15") (pintype "bidirectional"))
    )
    (net (code "78") (name "Net-(U3-SET1)") (class "Default")
      (node (ref "C11") (pin "1") (pinfunction "1_1") (pintype "passive"))
      (node (ref "U3") (pin "16") (pinfunction "SET1_16") (pintype "bidirectional"))
    )
    (net (code "79") (name "Net-(U3-SET2)") (class "Default")
      (node (ref "C11") (pin "2") (pinfunction "2_2") (pintype "passive"))
      (node (ref "U3") (pin "12") (pinfunction "SET2_12") (pintype "bidirectional"))
    )
    (net (code "80") (name "Net-(U5-PLL)") (class "Default")
      (node (ref "C15") (pin "1") (pinfunction "1_1") (pintype "passive"))
      (node (ref "C16") (pin "1") (pinfunction "1_1") (pintype "passive"))
      (node (ref "U5") (pin "14") (pinfunction "PLL_14") (pintype "bidirectional"))
    )
    (net (code "81") (name "Net-(U7-USBDM)") (class "Default")
      (node (ref "U7") (pin "16") (pinfunction "USBDM_16") (pintype "bidirectional"))
      (node (ref "X2") (pin "D-") (pinfunction "D-_D-") (pintype "bidirectional"))
    )
    (net (code "82") (name "Net-(U7-USBDP)") (class "Default")
      (node (ref "U7") (pin "15") (pinfunction "USBDP_15") (pintype "bidirectional"))
      (node (ref "X2") (pin "D+") (pinfunction "D+_D+") (pintype "bidirectional"))
    )
    (net (code "83") (name "unconnected-(BMP1-EOC-Pad2)") (class "Default")
      (node (ref "BMP1") (pin "2") (pinfunction "EOC_2") (pintype "output"))
    )
    (net (code "84") (name "unconnected-(BMP1-NC-Pad5)") (class "Default")
      (node (ref "BMP1") (pin "5") (pinfunction "NC_5") (pintype "bidirectional"))
    )
    (net (code "85") (name "unconnected-(BMP1-XCLR-Pad8)") (class "Default")
      (node (ref "BMP1") (pin "8") (pinfunction "XCLR_8") (pintype "input"))
    )
    (net (code "86") (name "unconnected-(ICSP-Pad3)") (class "Default")
      (node (ref "ICSP") (pin "3") (pinfunction "3_3") (pintype "passive"))
    )
    (net (code "87") (name "unconnected-(SEL1-Pad3)") (class "Default")
      (node (ref "SEL1") (pin "3") (pinfunction "3_3") (pintype "passive"))
    )
    (net (code "88") (name "unconnected-(SEL2-Pad3)") (class "Default")
      (node (ref "SEL2") (pin "3") (pinfunction "3_3") (pintype "passive"))
    )
    (net (code "89") (name "unconnected-(SEL3-Pad3)") (class "Default")
      (node (ref "SEL3") (pin "3") (pinfunction "3_3") (pintype "passive"))
    )
    (net (code "90") (name "unconnected-(SEL4-Pad3)") (class "Default")
      (node (ref "SEL4") (pin "3") (pinfunction "3_3") (pintype "passive"))
    )
    (net (code "91") (name "unconnected-(U$2-CTS-Pad12)") (class "Default")
      (node (ref "U$2") (pin "12") (pinfunction "CTS_12") (pintype "output"))
    )
    (net (code "92") (name "unconnected-(U$2-DTR-Pad9)") (class "Default")
      (node (ref "U$2") (pin "9") (pinfunction "DTR_9") (pintype "bidirectional"))
    )
    (net (code "93") (name "unconnected-(U$2-RESET-Pad5)") (class "Default")
      (node (ref "U$2") (pin "5") (pinfunction "RESET_5") (pintype "input"))
    )
    (net (code "94") (name "unconnected-(U$2-RTS-Pad16)") (class "Default")
      (node (ref "U$2") (pin "16") (pinfunction "RTS_16") (pintype "input"))
    )
    (net (code "95") (name "unconnected-(U1-NC-Pad1)") (class "Default")
      (node (ref "U1") (pin "1") (pinfunction "NC_1") (pintype "bidirectional"))
    )
    (net (code "96") (name "unconnected-(U1-RSV-Pad8)") (class "Default")
      (node (ref "U1") (pin "8") (pinfunction "RSV_8") (pintype "bidirectional"))
    )
    (net (code "97") (name "unconnected-(U2-4A-Pad9)") (class "Default")
      (node (ref "U2") (pin "9") (pinfunction "4A_9") (pintype "bidirectional"))
    )
    (net (code "98") (name "unconnected-(U2-4Y-Pad10)") (class "Default")
      (node (ref "U2") (pin "10") (pinfunction "4Y_10") (pintype "bidirectional"))
    )
    (net (code "99") (name "unconnected-(U2-5A-Pad11)") (class "Default")
      (node (ref "U2") (pin "11") (pinfunction "5A_11") (pintype "bidirectional"))
    )
    (net (code "100") (name "unconnected-(U2-5Y-Pad12)") (class "Default")
      (node (ref "U2") (pin "12") (pinfunction "5Y_12") (pintype "bidirectional"))
    )
    (net (code "101") (name "unconnected-(U2-6A-Pad14)") (class "Default")
      (node (ref "U2") (pin "14") (pinfunction "6A_14") (pintype "bidirectional"))
    )
    (net (code "102") (name "unconnected-(U2-6Y-Pad15)") (class "Default")
      (node (ref "U2") (pin "15") (pinfunction "6Y_15") (pintype "bidirectional"))
    )
    (net (code "103") (name "unconnected-(U3-DRDY_M-Pad18)") (class "Default")
      (node (ref "U3") (pin "18") (pinfunction "DRDY_M_18") (pintype "bidirectional"))
    )
    (net (code "104") (name "unconnected-(U3-INT1-Pad26)") (class "Default")
      (node (ref "U3") (pin "26") (pinfunction "INT1_26") (pintype "bidirectional"))
    )
    (net (code "105") (name "unconnected-(U3-INT2-Pad27)") (class "Default")
      (node (ref "U3") (pin "27") (pinfunction "INT2_27") (pintype "bidirectional"))
    )
    (net (code "106") (name "unconnected-(U4-(A8)PC0-Pad53)") (class "Default")
      (node (ref "U4") (pin "53") (pinfunction "(A8)PC0_53") (pintype "bidirectional"))
    )
    (net (code "107") (name "unconnected-(U4-(A9)PC1-Pad54)") (class "Default")
      (node (ref "U4") (pin "54") (pinfunction "(A9)PC1_54") (pintype "bidirectional"))
    )
    (net (code "108") (name "unconnected-(U4-(A10)PC2-Pad55)") (class "Default")
      (node (ref "U4") (pin "55") (pinfunction "(A10)PC2_55") (pintype "bidirectional"))
    )
    (net (code "109") (name "unconnected-(U4-(A11)PC3-Pad56)") (class "Default")
      (node (ref "U4") (pin "56") (pinfunction "(A11)PC3_56") (pintype "bidirectional"))
    )
    (net (code "110") (name "unconnected-(U4-(A12)PC4-Pad57)") (class "Default")
      (node (ref "U4") (pin "57") (pinfunction "(A12)PC4_57") (pintype "bidirectional"))
    )
    (net (code "111") (name "unconnected-(U4-(A13)PC5-Pad58)") (class "Default")
      (node (ref "U4") (pin "58") (pinfunction "(A13)PC5_58") (pintype "bidirectional"))
    )
    (net (code "112") (name "unconnected-(U4-(A14)PC6-Pad59)") (class "Default")
      (node (ref "U4") (pin "59") (pinfunction "(A14)PC6_59") (pintype "bidirectional"))
    )
    (net (code "113") (name "unconnected-(U4-(A15)PC7-Pad60)") (class "Default")
      (node (ref "U4") (pin "60") (pinfunction "(A15)PC7_60") (pintype "bidirectional"))
    )
    (net (code "114") (name "unconnected-(U4-(AD0)PA0-Pad78)") (class "Default")
      (node (ref "U4") (pin "78") (pinfunction "(AD0)PA0_78") (pintype "bidirectional"))
    )
    (net (code "115") (name "unconnected-(U4-(AD1)PA1-Pad77)") (class "Default")
      (node (ref "U4") (pin "77") (pinfunction "(AD1)PA1_77") (pintype "bidirectional"))
    )
    (net (code "116") (name "unconnected-(U4-(AD2)PA2-Pad76)") (class "Default")
      (node (ref "U4") (pin "76") (pinfunction "(AD2)PA2_76") (pintype "bidirectional"))
    )
    (net (code "117") (name "unconnected-(U4-(AD3)PA3-Pad75)") (class "Default")
      (node (ref "U4") (pin "75") (pinfunction "(AD3)PA3_75") (pintype "bidirectional"))
    )
    (net (code "118") (name "unconnected-(U4-(AD4)PA4-Pad74)") (class "Default")
      (node (ref "U4") (pin "74") (pinfunction "(AD4)PA4_74") (pintype "bidirectional"))
    )
    (net (code "119") (name "unconnected-(U4-(AD5)PA5-Pad73)") (class "Default")
      (node (ref "U4") (pin "73") (pinfunction "(AD5)PA5_73") (pintype "bidirectional"))
    )
    (net (code "120") (name "unconnected-(U4-(AD6)PA6-Pad72)") (class "Default")
      (node (ref "U4") (pin "72") (pinfunction "(AD6)PA6_72") (pintype "bidirectional"))
    )
    (net (code "121") (name "unconnected-(U4-(AD7)PA7-Pad71)") (class "Default")
      (node (ref "U4") (pin "71") (pinfunction "(AD7)PA7_71") (pintype "bidirectional"))
    )
    (net (code "122") (name "unconnected-(U4-(ADC4{slash}TCK)PF4-Pad93)") (class "Default")
      (node (ref "U4") (pin "93") (pinfunction "(ADC4/TCK)PF4_93") (pintype "bidirectional"))
    )
    (net (code "123") (name "unconnected-(U4-(ADC5{slash}TMS)PF5-Pad92)") (class "Default")
      (node (ref "U4") (pin "92") (pinfunction "(ADC5/TMS)PF5_92") (pintype "bidirectional"))
    )
    (net (code "124") (name "unconnected-(U4-(ADC6{slash}TDO)PF6-Pad91)") (class "Default")
      (node (ref "U4") (pin "91") (pinfunction "(ADC6/TDO)PF6_91") (pintype "bidirectional"))
    )
    (net (code "125") (name "unconnected-(U4-(ADC7{slash}TDI)PF7-Pad90)") (class "Default")
      (node (ref "U4") (pin "90") (pinfunction "(ADC7/TDI)PF7_90") (pintype "bidirectional"))
    )
    (net (code "126") (name "unconnected-(U4-(ALE)PG2-Pad70)") (class "Default")
      (node (ref "U4") (pin "70") (pinfunction "(ALE)PG2_70") (pintype "bidirectional"))
    )
    (net (code "127") (name "unconnected-(U4-(CLKO{slash}ICP3{slash}INT7)PE7-Pad9)") (class "Default")
      (node (ref "U4") (pin "9") (pinfunction "(CLKO/ICP3/INT7)PE7_9") (pintype "bidirectional"))
    )
    (net (code "128") (name "unconnected-(U4-(ICP1)PD4-Pad47)") (class "Default")
      (node (ref "U4") (pin "47") (pinfunction "(ICP1)PD4_47") (pintype "bidirectional"))
    )
    (net (code "129") (name "unconnected-(U4-(OC0A{slash}OC1C{slash}PCINT7)PB7-Pad26)") (class "Default")
      (node (ref "U4") (pin "26") (pinfunction "(OC0A/OC1C/PCINT7)PB7_26") (pintype "bidirectional"))
    )
    (net (code "130") (name "unconnected-(U4-(OC0B)PG5-Pad1)") (class "Default")
      (node (ref "U4") (pin "1") (pinfunction "(OC0B)PG5_1") (pintype "bidirectional"))
    )
    (net (code "131") (name "unconnected-(U4-(OC1A{slash}PCINT5)PB5-Pad24)") (class "Default")
      (node (ref "U4") (pin "24") (pinfunction "(OC1A/PCINT5)PB5_24") (pintype "bidirectional"))
    )
    (net (code "132") (name "unconnected-(U4-(OC1B{slash}PCINT6)PB6-Pad25)") (class "Default")
      (node (ref "U4") (pin "25") (pinfunction "(OC1B/PCINT6)PB6_25") (pintype "bidirectional"))
    )
    (net (code "133") (name "unconnected-(U4-(OC2A{slash}PCINT4)PB4-Pad23)") (class "Default")
      (node (ref "U4") (pin "23") (pinfunction "(OC2A/PCINT4)PB4_23") (pintype "bidirectional"))
    )
    (net (code "134") (name "unconnected-(U4-(RD)PG1-Pad52)") (class "Default")
      (node (ref "U4") (pin "52") (pinfunction "(RD)PG1_52") (pintype "bidirectional"))
    )
    (net (code "135") (name "unconnected-(U4-(T0)PD7-Pad50)") (class "Default")
      (node (ref "U4") (pin "50") (pinfunction "(T0)PD7_50") (pintype "bidirectional"))
    )
    (net (code "136") (name "unconnected-(U4-(T1)PD6-Pad49)") (class "Default")
      (node (ref "U4") (pin "49") (pinfunction "(T1)PD6_49") (pintype "bidirectional"))
    )
    (net (code "137") (name "unconnected-(U4-(T3{slash}INT6)PE6-Pad8)") (class "Default")
      (node (ref "U4") (pin "8") (pinfunction "(T3/INT6)PE6_8") (pintype "bidirectional"))
    )
    (net (code "138") (name "unconnected-(U4-(TOSC1)PG4-Pad29)") (class "Default")
      (node (ref "U4") (pin "29") (pinfunction "(TOSC1)PG4_29") (pintype "bidirectional"))
    )
    (net (code "139") (name "unconnected-(U4-(TOSC2)PG3-Pad28)") (class "Default")
      (node (ref "U4") (pin "28") (pinfunction "(TOSC2)PG3_28") (pintype "bidirectional"))
    )
    (net (code "140") (name "unconnected-(U4-(XCK0{slash}AIN0)PE2-Pad4)") (class "Default")
      (node (ref "U4") (pin "4") (pinfunction "(XCK0/AIN0)PE2_4") (pintype "bidirectional"))
    )
    (net (code "141") (name "unconnected-(U4-(XCK1)PD5-Pad48)") (class "Default")
      (node (ref "U4") (pin "48") (pinfunction "(XCK1)PD5_48") (pintype "bidirectional"))
    )
    (net (code "142") (name "unconnected-(U4-PH0(RXD2)-Pad12)") (class "Default")
      (node (ref "U4") (pin "12") (pinfunction "PH0(RXD2)_12") (pintype "bidirectional"))
    )
    (net (code "143") (name "unconnected-(U4-PH1(TXD2)-Pad13)") (class "Default")
      (node (ref "U4") (pin "13") (pinfunction "PH1(TXD2)_13") (pintype "bidirectional"))
    )
    (net (code "144") (name "unconnected-(U4-PH2(XCK2)-Pad14)") (class "Default")
      (node (ref "U4") (pin "14") (pinfunction "PH2(XCK2)_14") (pintype "bidirectional"))
    )
    (net (code "145") (name "unconnected-(U4-PH7(T4)-Pad27)") (class "Default")
      (node (ref "U4") (pin "27") (pinfunction "PH7(T4)_27") (pintype "bidirectional"))
    )
    (net (code "146") (name "unconnected-(U4-PJ0(RXD3{slash}PCINT9)-Pad63)") (class "Default")
      (node (ref "U4") (pin "63") (pinfunction "PJ0(RXD3/PCINT9)_63") (pintype "bidirectional"))
    )
    (net (code "147") (name "unconnected-(U4-PJ1(TXD3{slash}PCINT10)-Pad64)") (class "Default")
      (node (ref "U4") (pin "64") (pinfunction "PJ1(TXD3/PCINT10)_64") (pintype "bidirectional"))
    )
    (net (code "148") (name "unconnected-(U4-PJ2(XCK3{slash}PCINT11)-Pad65)") (class "Default")
      (node (ref "U4") (pin "65") (pinfunction "PJ2(XCK3/PCINT11)_65") (pintype "bidirectional"))
    )
    (net (code "149") (name "unconnected-(U4-PJ3(PCINT12)-Pad66)") (class "Default")
      (node (ref "U4") (pin "66") (pinfunction "PJ3(PCINT12)_66") (pintype "bidirectional"))
    )
    (net (code "150") (name "unconnected-(U4-PJ4(PCINT13)-Pad67)") (class "Default")
      (node (ref "U4") (pin "67") (pinfunction "PJ4(PCINT13)_67") (pintype "bidirectional"))
    )
    (net (code "151") (name "unconnected-(U4-PJ5(PCINT14)-Pad68)") (class "Default")
      (node (ref "U4") (pin "68") (pinfunction "PJ5(PCINT14)_68") (pintype "bidirectional"))
    )
    (net (code "152") (name "unconnected-(U4-PJ6(PCINT15)-Pad69)") (class "Default")
      (node (ref "U4") (pin "69") (pinfunction "PJ6(PCINT15)_69") (pintype "bidirectional"))
    )
    (net (code "153") (name "unconnected-(U4-PJ7-Pad79)") (class "Default")
      (node (ref "U4") (pin "79") (pinfunction "PJ7_79") (pintype "bidirectional"))
    )
    (net (code "154") (name "unconnected-(U4-PK0(ADC8{slash}PCINT16)-Pad89)") (class "Default")
      (node (ref "U4") (pin "89") (pinfunction "PK0(ADC8/PCINT16)_89") (pintype "bidirectional"))
    )
    (net (code "155") (name "unconnected-(U4-PK1(ADC9{slash}PCINT17)-Pad88)") (class "Default")
      (node (ref "U4") (pin "88") (pinfunction "PK1(ADC9/PCINT17)_88") (pintype "bidirectional"))
    )
    (net (code "156") (name "unconnected-(U4-PK2(ADC10{slash}PCINT18)-Pad87)") (class "Default")
      (node (ref "U4") (pin "87") (pinfunction "PK2(ADC10/PCINT18)_87") (pintype "bidirectional"))
    )
    (net (code "157") (name "unconnected-(U4-PK3(ADC11{slash}PCINT19)-Pad86)") (class "Default")
      (node (ref "U4") (pin "86") (pinfunction "PK3(ADC11/PCINT19)_86") (pintype "bidirectional"))
    )
    (net (code "158") (name "unconnected-(U4-PK4(ADC12{slash}PCINT20)-Pad85)") (class "Default")
      (node (ref "U4") (pin "85") (pinfunction "PK4(ADC12/PCINT20)_85") (pintype "bidirectional"))
    )
    (net (code "159") (name "unconnected-(U4-PK5(ADC13{slash}PCINT21)-Pad84)") (class "Default")
      (node (ref "U4") (pin "84") (pinfunction "PK5(ADC13/PCINT21)_84") (pintype "bidirectional"))
    )
    (net (code "160") (name "unconnected-(U4-PK6(ADC14{slash}PCINT22)-Pad83)") (class "Default")
      (node (ref "U4") (pin "83") (pinfunction "PK6(ADC14/PCINT22)_83") (pintype "bidirectional"))
    )
    (net (code "161") (name "unconnected-(U4-PK7(ADC15{slash}PCINT23)-Pad82)") (class "Default")
      (node (ref "U4") (pin "82") (pinfunction "PK7(ADC15/PCINT23)_82") (pintype "bidirectional"))
    )
    (net (code "162") (name "unconnected-(U4-PL0(ICP4)-Pad35)") (class "Default")
      (node (ref "U4") (pin "35") (pinfunction "PL0(ICP4)_35") (pintype "bidirectional"))
    )
    (net (code "163") (name "unconnected-(U4-PL1(ICP5)-Pad36)") (class "Default")
      (node (ref "U4") (pin "36") (pinfunction "PL1(ICP5)_36") (pintype "bidirectional"))
    )
    (net (code "164") (name "unconnected-(U4-PL2(T5)-Pad37)") (class "Default")
      (node (ref "U4") (pin "37") (pinfunction "PL2(T5)_37") (pintype "bidirectional"))
    )
    (net (code "165") (name "unconnected-(U4-PL5(OC5C)-Pad40)") (class "Default")
      (node (ref "U4") (pin "40") (pinfunction "PL5(OC5C)_40") (pintype "bidirectional"))
    )
    (net (code "166") (name "unconnected-(U4-PL6-Pad41)") (class "Default")
      (node (ref "U4") (pin "41") (pinfunction "PL6_41") (pintype "bidirectional"))
    )
    (net (code "167") (name "unconnected-(U4-PL7-Pad42)") (class "Default")
      (node (ref "U4") (pin "42") (pinfunction "PL7_42") (pintype "bidirectional"))
    )
    (net (code "168") (name "unconnected-(U5-INT1-Pad7)") (class "Default")
      (node (ref "U5") (pin "7") (pinfunction "INT1_7") (pintype "bidirectional"))
    )
    (net (code "169") (name "unconnected-(U5-INT2-Pad6)") (class "Default")
      (node (ref "U5") (pin "6") (pinfunction "INT2_6") (pintype "bidirectional"))
    )
    (net (code "170") (name "unconnected-(U7-3V3OUT-Pad17)") (class "Default")
      (node (ref "U7") (pin "17") (pinfunction "3V3OUT_17") (pintype "output"))
    )
    (net (code "171") (name "unconnected-(U7-DCD-Pad10)") (class "Default")
      (node (ref "U7") (pin "10") (pinfunction "DCD_10") (pintype "input"))
    )
    (net (code "172") (name "unconnected-(U7-DSR-Pad9)") (class "Default")
      (node (ref "U7") (pin "9") (pinfunction "DSR_9") (pintype "input"))
    )
    (net (code "173") (name "unconnected-(U7-OSCI-Pad27)") (class "Default")
      (node (ref "U7") (pin "27") (pinfunction "OSCI_27") (pintype "input"))
    )
    (net (code "174") (name "unconnected-(U7-OSCO-Pad28)") (class "Default")
      (node (ref "U7") (pin "28") (pinfunction "OSCO_28") (pintype "output"))
    )
    (net (code "175") (name "unconnected-(U7-PWREN-Pad14)") (class "Default")
      (node (ref "U7") (pin "14") (pinfunction "PWREN_14") (pintype "input"))
    )
    (net (code "176") (name "unconnected-(U7-RESET-Pad19)") (class "Default")
      (node (ref "U7") (pin "19") (pinfunction "RESET_19") (pintype "input"))
    )
    (net (code "177") (name "unconnected-(U7-RI-Pad6)") (class "Default")
      (node (ref "U7") (pin "6") (pinfunction "RI_6") (pintype "input"))
    )
    (net (code "178") (name "unconnected-(U7-SLEEP-Pad12)") (class "Default")
      (node (ref "U7") (pin "12") (pinfunction "SLEEP_12") (pintype "input"))
    )
    (net (code "179") (name "unconnected-(U7-TXDEN-Pad13)") (class "Default")
      (node (ref "U7") (pin "13") (pinfunction "TXDEN_13") (pintype "input"))
    )
  )
)
